# SoM-Supply.net
KiCad netlist of a schematic drawn in Altium Designer
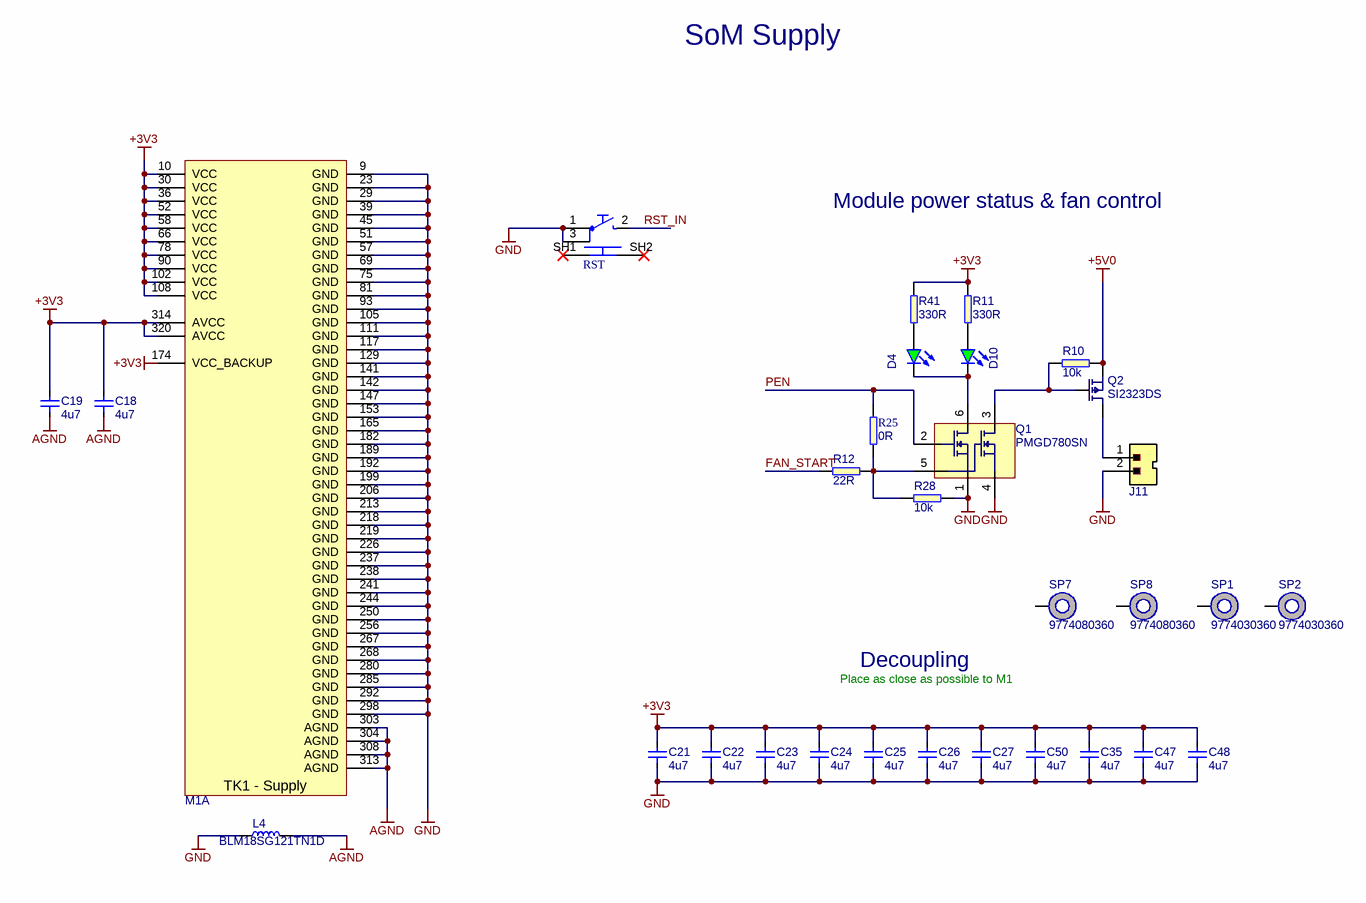
[diagram p0: SoM-Supply.SchDoc]

(export (version "E")
  (design (tool "Eeschema 10.0.6"))
  (components
    (comp (ref "C18")
      (value "4u7")
      (footprint "0603")
      (description "MLCC SMT Capacitor 4.7uF 0603")
      (fields (field (name "MANUFACTURER") "MULTICOMP") (field (name "PART NUMBER") "C_4u7_0603"))
      (libsource (lib "TK1Baseboard") (part "C_4u7_0603"))
    )
    (comp (ref "C19")
      (value "4u7")
      (footprint "0603")
      (description "MLCC SMT Capacitor 4.7uF 0603")
      (fields (field (name "MANUFACTURER") "MULTICOMP") (field (name "PART NUMBER") "C_4u7_0603"))
      (libsource (lib "TK1Baseboard") (part "C_4u7_0603"))
    )
    (comp (ref "C21")
      (value "4u7")
      (footprint "0603")
      (description "MLCC SMT Capacitor 4.7uF 0603")
      (fields (field (name "MANUFACTURER") "MULTICOMP") (field (name "PART NUMBER") "C_4u7_0603"))
      (libsource (lib "TK1Baseboard") (part "C_4u7_0603"))
    )
    (comp (ref "C22")
      (value "4u7")
      (footprint "0603")
      (description "MLCC SMT Capacitor 4.7uF 0603")
      (fields (field (name "MANUFACTURER") "MULTICOMP") (field (name "PART NUMBER") "C_4u7_0603"))
      (libsource (lib "TK1Baseboard") (part "C_4u7_0603"))
    )
    (comp (ref "C23")
      (value "4u7")
      (footprint "0603")
      (description "MLCC SMT Capacitor 4.7uF 0603")
      (fields (field (name "MANUFACTURER") "MULTICOMP") (field (name "PART NUMBER") "C_4u7_0603"))
      (libsource (lib "TK1Baseboard") (part "C_4u7_0603"))
    )
    (comp (ref "C24")
      (value "4u7")
      (footprint "0603")
      (description "MLCC SMT Capacitor 4.7uF 0603")
      (fields (field (name "MANUFACTURER") "MULTICOMP") (field (name "PART NUMBER") "C_4u7_0603"))
      (libsource (lib "TK1Baseboard") (part "C_4u7_0603"))
    )
    (comp (ref "C25")
      (value "4u7")
      (footprint "0603")
      (description "MLCC SMT Capacitor 4.7uF 0603")
      (fields (field (name "MANUFACTURER") "MULTICOMP") (field (name "PART NUMBER") "C_4u7_0603"))
      (libsource (lib "TK1Baseboard") (part "C_4u7_0603"))
    )
    (comp (ref "C26")
      (value "4u7")
      (footprint "0603")
      (description "MLCC SMT Capacitor 4.7uF 0603")
      (fields (field (name "MANUFACTURER") "MULTICOMP") (field (name "PART NUMBER") "C_4u7_0603"))
      (libsource (lib "TK1Baseboard") (part "C_4u7_0603"))
    )
    (comp (ref "C27")
      (value "4u7")
      (footprint "0603")
      (description "MLCC SMT Capacitor 4.7uF 0603")
      (fields (field (name "MANUFACTURER") "MULTICOMP") (field (name "PART NUMBER") "C_4u7_0603"))
      (libsource (lib "TK1Baseboard") (part "C_4u7_0603"))
    )
    (comp (ref "C35")
      (value "4u7")
      (footprint "0603")
      (description "MLCC SMT Capacitor 4.7uF 0603")
      (fields (field (name "MANUFACTURER") "MULTICOMP") (field (name "PART NUMBER") "C_4u7_0603"))
      (libsource (lib "TK1Baseboard") (part "C_4u7_0603"))
    )
    (comp (ref "C47")
      (value "4u7")
      (footprint "0603")
      (description "MLCC SMT Capacitor 4.7uF 0603")
      (fields (field (name "MANUFACTURER") "MULTICOMP") (field (name "PART NUMBER") "C_4u7_0603"))
      (libsource (lib "TK1Baseboard") (part "C_4u7_0603"))
    )
    (comp (ref "C48")
      (value "4u7")
      (footprint "0603")
      (description "MLCC SMT Capacitor 4.7uF 0603")
      (fields (field (name "MANUFACTURER") "MULTICOMP") (field (name "PART NUMBER") "C_4u7_0603"))
      (libsource (lib "TK1Baseboard") (part "C_4u7_0603"))
    )
    (comp (ref "C50")
      (value "4u7")
      (footprint "0603")
      (description "MLCC SMT Capacitor 4.7uF 0603")
      (fields (field (name "MANUFACTURER") "MULTICOMP") (field (name "PART NUMBER") "C_4u7_0603"))
      (libsource (lib "TK1Baseboard") (part "C_4u7_0603"))
    )
    (comp (ref "D4")
      (value "KPT-1608SGC")
      (footprint "LED0603")
      (description "LED Green 0603 case")
      (fields (field (name "PART NUMBER") "LED_G") (field (name "MANUFACTURER") "KINGBRIGHT"))
      (libsource (lib "TK1Baseboard") (part "LED_G"))
    )
    (comp (ref "D10")
      (value "KPT-1608SGC")
      (footprint "LED0603")
      (description "LED Green 0603 case")
      (fields (field (name "PART NUMBER") "LED_G") (field (name "MANUFACTURER") "KINGBRIGHT"))
      (libsource (lib "TK1Baseboard") (part "LED_G"))
    )
    (comp (ref "J11")
      (value "MX-22-23-2021")
      (footprint "molex_2223-2021")
      (description "Pinhead connector with key")
      (fields (field (name "PART NUMBER") "molex_2223-2021") (field (name "MANUFACTURER") "Molex"))
      (libsource (lib "TK1Baseboard") (part "molex_2223-2021"))
    )
    (comp (ref "L4")
      (value "BLM18SG121TN1D")
      (footprint "0603")
      (description "FERRITE BEAD, 0.025OHM, 3A, 0603")
      (fields (field (name "MANUFACTURER") "MURATA"))
      (libsource (lib "TK1Baseboard") (part "BLM18SG121TN1D"))
    )
    (comp (ref "M1")
      (value "MM70-314-310B1")
      (footprint "Apalis-H")
      (description "Toradex Apalis TK1, Horizontal")
      (fields (field (name "PART NUMBER") "Apalis-TK1-H") (field (name "MANUFACTURER") "JAE Electronics"))
      (libsource (lib "TK1Baseboard") (part "Apalis-TK1-H"))
    )
    (comp (ref "Q1")
      (value "PMGD780SN")
      (footprint "SOT-363")
      (description "60 V, dual N-channel Trench MOSFET")
      (fields (field (name "MANUFACTURER") "NXP") (field (name "MPN") "PMGD780SN,115"))
      (libsource (lib "TK1Baseboard") (part "PMGD780SN"))
    )
    (comp (ref "Q2")
      (value "SI2323DS")
      (footprint "SOT-23")
      (description "pMOS 4.7A 20V")
      (fields (field (name "MANUFACTURER") "Vishay") (field (name "MPN") "SI2323DS-T1-E3"))
      (libsource (lib "TK1Baseboard") (part "PMOS"))
    )
    (comp (ref "R10")
      (value "10k")
      (footprint "0402")
      (description "RES, 10k, 0402")
      (fields (field (name "MANUFACTURER") "MULTICOMP") (field (name "PART NUMBER") "R_10k_0402"))
      (libsource (lib "TK1Baseboard") (part "R_10k_0402"))
    )
    (comp (ref "R11")
      (value "330R")
      (footprint "0402")
      (description "RES, 330R, 0402")
      (fields (field (name "MANUFACTURER") "MULTICOMP") (field (name "PART NUMBER") "R_330R_0402"))
      (libsource (lib "TK1Baseboard") (part "R_330R_0402"))
    )
    (comp (ref "R12")
      (value "22R")
      (footprint "0402")
      (description "RES, 22R, 0402")
      (fields (field (name "MANUFACTURER") "VISHAY") (field (name "PART NUMBER") "R_22R_0402"))
      (libsource (lib "TK1Baseboard") (part "R_22R_0402"))
    )
    (comp (ref "R25")
      (value "0R")
      (footprint "0402")
      (description "RES, 0R, 0402")
      (fields (field (name "MANUFACTURER") "Panasonic") (field (name "PART NUMBER") "R_0R_0402"))
      (libsource (lib "TK1Baseboard") (part "R_0R_0402"))
    )
    (comp (ref "R28")
      (value "10k")
      (footprint "0402")
      (description "RES, 10k, 0402")
      (fields (field (name "MANUFACTURER") "MULTICOMP") (field (name "PART NUMBER") "R_10k_0402"))
      (libsource (lib "TK1Baseboard") (part "R_10k_0402"))
    )
    (comp (ref "R41")
      (value "330R")
      (footprint "0402")
      (description "RES, 330R, 0402")
      (fields (field (name "MANUFACTURER") "MULTICOMP") (field (name "PART NUMBER") "R_330R_0402"))
      (libsource (lib "TK1Baseboard") (part "R_330R_0402"))
    )
    (comp (ref "RST")
      (value "TL3340AF160QG")
      (footprint "TL3340AF160QG")
      (description "E-SWITCH  TL3340AF160QG  SWITCH, TACTILE SPST 50mA, SMD GULL WING")
      (fields (field (name "MANUFACTURER") "E-SWITCH"))
      (libsource (lib "TK1Baseboard") (part "TL3340AF160QG"))
    )
    (comp (ref "SP1")
      (value "9774030360")
      (footprint "M3-3mm")
      (description "M3x3")
      (fields (field (name "PART NUMBER") "WE_9774030360") (field (name "MANUFACTURER") "WURTH ELEKTRONIK"))
      (libsource (lib "TK1Baseboard") (part "WE_9774030360"))
    )
    (comp (ref "SP2")
      (value "9774030360")
      (footprint "M3-3mm")
      (description "M3x3")
      (fields (field (name "PART NUMBER") "WE_9774030360") (field (name "MANUFACTURER") "WURTH ELEKTRONIK"))
      (libsource (lib "TK1Baseboard") (part "WE_9774030360"))
    )
    (comp (ref "SP7")
      (value "9774080360")
      (footprint "M3-8mm")
      (description "M2.5x5")
      (fields (field (name "MANUFACTURER") "WURTH ELEKTRONIK"))
      (libsource (lib "TK1Baseboard") (part "M3x8"))
    )
    (comp (ref "SP8")
      (value "9774080360")
      (footprint "M3-8mm")
      (description "M2.5x5")
      (fields (field (name "MANUFACTURER") "WURTH ELEKTRONIK"))
      (libsource (lib "TK1Baseboard") (part "M3x8"))
    )
  )
  (nets
    (net (code "1") (name "+3V3") (class "Default")
      (node (ref "C18") (pin "2") (pinfunction "2_2") (pintype "passive"))
      (node (ref "C19") (pin "2") (pinfunction "2_2") (pintype "passive"))
      (node (ref "C21") (pin "2") (pinfunction "2_2") (pintype "passive"))
      (node (ref "C22") (pin "2") (pinfunction "2_2") (pintype "passive"))
      (node (ref "C23") (pin "2") (pinfunction "2_2") (pintype "passive"))
      (node (ref "C24") (pin "2") (pinfunction "2_2") (pintype "passive"))
      (node (ref "C25") (pin "2") (pinfunction "2_2") (pintype "passive"))
      (node (ref "C26") (pin "2") (pinfunction "2_2") (pintype "passive"))
      (node (ref "C27") (pin "2") (pinfunction "2_2") (pintype "passive"))
      (node (ref "C35") (pin "2") (pinfunction "2_2") (pintype "passive"))
      (node (ref "C47") (pin "2") (pinfunction "2_2") (pintype "passive"))
      (node (ref "C48") (pin "2") (pinfunction "2_2") (pintype "passive"))
      (node (ref "C50") (pin "2") (pinfunction "2_2") (pintype "passive"))
      (node (ref "M1") (pin "10") (pinfunction "VCC_10") (pintype "passive"))
      (node (ref "M1") (pin "102") (pinfunction "VCC_102") (pintype "passive"))
      (node (ref "M1") (pin "108") (pinfunction "VCC_108") (pintype "passive"))
      (node (ref "M1") (pin "174") (pinfunction "VCC_BACKUP_174") (pintype "passive"))
      (node (ref "M1") (pin "30") (pinfunction "VCC_30") (pintype "passive"))
      (node (ref "M1") (pin "314") (pinfunction "AVCC_314") (pintype "power_in"))
      (node (ref "M1") (pin "320") (pinfunction "AVCC_320") (pintype "passive"))
      (node (ref "M1") (pin "36") (pinfunction "VCC_36") (pintype "passive"))
      (node (ref "M1") (pin "52") (pinfunction "VCC_52") (pintype "passive"))
      (node (ref "M1") (pin "58") (pinfunction "VCC_58") (pintype "passive"))
      (node (ref "M1") (pin "66") (pinfunction "VCC_66") (pintype "passive"))
      (node (ref "M1") (pin "78") (pinfunction "VCC_78") (pintype "passive"))
      (node (ref "M1") (pin "90") (pinfunction "VCC_90") (pintype "passive"))
      (node (ref "R11") (pin "2") (pintype "passive"))
      (node (ref "R41") (pin "2") (pintype "passive"))
    )
    (net (code "2") (name "+5V0") (class "Default")
      (node (ref "Q2") (pin "2") (pinfunction "S_2") (pintype "passive"))
      (node (ref "R10") (pin "2") (pintype "passive"))
    )
    (net (code "3") (name "/FAN_START") (class "Default") (node (ref "R12") (pin "1") (pintype "passive")))
    (net (code "4") (name "/PEN") (class "Default")
      (node (ref "Q1") (pin "2") (pinfunction "G1_2") (pintype "passive"))
      (node (ref "R25") (pin "2") (pintype "passive"))
    )
    (net (code "5") (name "/RST_IN") (class "Default")
      (node (ref "RST") (pin "2") (pinfunction "2_2") (pintype "passive"))
    )
    (net (code "6") (name "AGND") (class "Default")
      (node (ref "C18") (pin "1") (pinfunction "1_1") (pintype "passive"))
      (node (ref "C19") (pin "1") (pinfunction "1_1") (pintype "passive"))
      (node (ref "L4") (pin "2") (pintype "passive"))
      (node (ref "M1") (pin "303") (pinfunction "AGND_303") (pintype "power_in"))
      (node (ref "M1") (pin "304") (pinfunction "AGND_304") (pintype "power_in"))
      (node (ref "M1") (pin "308") (pinfunction "AGND_308") (pintype "power_in"))
      (node (ref "M1") (pin "313") (pinfunction "AGND_313") (pintype "passive"))
    )
    (net (code "7") (name "GND") (class "Default")
      (node (ref "C21") (pin "1") (pinfunction "1_1") (pintype "passive"))
      (node (ref "C22") (pin "1") (pinfunction "1_1") (pintype "passive"))
      (node (ref "C23") (pin "1") (pinfunction "1_1") (pintype "passive"))
      (node (ref "C24") (pin "1") (pinfunction "1_1") (pintype "passive"))
      (node (ref "C25") (pin "1") (pinfunction "1_1") (pintype "passive"))
      (node (ref "C26") (pin "1") (pinfunction "1_1") (pintype "passive"))
      (node (ref "C27") (pin "1") (pinfunction "1_1") (pintype "passive"))
      (node (ref "C35") (pin "1") (pinfunction "1_1") (pintype "passive"))
      (node (ref "C47") (pin "1") (pinfunction "1_1") (pintype "passive"))
      (node (ref "C48") (pin "1") (pinfunction "1_1") (pintype "passive"))
      (node (ref "C50") (pin "1") (pinfunction "1_1") (pintype "passive"))
      (node (ref "J11") (pin "2") (pinfunction "2_2") (pintype "passive"))
      (node (ref "L4") (pin "1") (pintype "passive"))
      (node (ref "M1") (pin "105") (pinfunction "GND_105") (pintype "power_in"))
      (node (ref "M1") (pin "111") (pinfunction "GND_111") (pintype "power_in"))
      (node (ref "M1") (pin "117") (pinfunction "GND_117") (pintype "power_in"))
      (node (ref "M1") (pin "129") (pinfunction "GND_129") (pintype "power_in"))
      (node (ref "M1") (pin "141") (pinfunction "GND_141") (pintype "power_in"))
      (node (ref "M1") (pin "142") (pinfunction "GND_142") (pintype "power_in"))
      (node (ref "M1") (pin "147") (pinfunction "GND_147") (pintype "power_in"))
      (node (ref "M1") (pin "153") (pinfunction "GND_153") (pintype "power_in"))
      (node (ref "M1") (pin "165") (pinfunction "GND_165") (pintype "power_in"))
      (node (ref "M1") (pin "182") (pinfunction "GND_182") (pintype "power_in"))
      (node (ref "M1") (pin "189") (pinfunction "GND_189") (pintype "power_in"))
      (node (ref "M1") (pin "192") (pinfunction "GND_192") (pintype "power_in"))
      (node (ref "M1") (pin "199") (pinfunction "GND_199") (pintype "power_in"))
      (node (ref "M1") (pin "206") (pinfunction "GND_206") (pintype "power_in"))
      (node (ref "M1") (pin "213") (pinfunction "GND_213") (pintype "power_in"))
      (node (ref "M1") (pin "218") (pinfunction "GND_218") (pintype "power_in"))
      (node (ref "M1") (pin "219") (pinfunction "GND_219") (pintype "power_in"))
      (node (ref "M1") (pin "226") (pinfunction "GND_226") (pintype "power_in"))
      (node (ref "M1") (pin "23") (pinfunction "GND_23") (pintype "passive"))
      (node (ref "M1") (pin "237") (pinfunction "GND_237") (pintype "power_in"))
      (node (ref "M1") (pin "238") (pinfunction "GND_238") (pintype "power_in"))
      (node (ref "M1") (pin "241") (pinfunction "GND_241") (pintype "power_in"))
      (node (ref "M1") (pin "244") (pinfunction "GND_244") (pintype "power_in"))
      (node (ref "M1") (pin "250") (pinfunction "GND_250") (pintype "power_in"))
      (node (ref "M1") (pin "256") (pinfunction "GND_256") (pintype "power_in"))
      (node (ref "M1") (pin "267") (pinfunction "GND_267") (pintype "power_in"))
      (node (ref "M1") (pin "268") (pinfunction "GND_268") (pintype "power_in"))
      (node (ref "M1") (pin "280") (pinfunction "GND_280") (pintype "power_in"))
      (node (ref "M1") (pin "285") (pinfunction "GND_285") (pintype "power_in"))
      (node (ref "M1") (pin "29") (pinfunction "GND_29") (pintype "power_in"))
      (node (ref "M1") (pin "292") (pinfunction "GND_292") (pintype "power_in"))
      (node (ref "M1") (pin "298") (pinfunction "GND_298") (pintype "power_in"))
      (node (ref "M1") (pin "39") (pinfunction "GND_39") (pintype "power_in"))
      (node (ref "M1") (pin "45") (pinfunction "GND_45") (pintype "power_in"))
      (node (ref "M1") (pin "51") (pinfunction "GND_51") (pintype "power_in"))
      (node (ref "M1") (pin "57") (pinfunction "GND_57") (pintype "power_in"))
      (node (ref "M1") (pin "69") (pinfunction "GND_69") (pintype "power_in"))
      (node (ref "M1") (pin "75") (pinfunction "GND_75") (pintype "power_in"))
      (node (ref "M1") (pin "81") (pinfunction "GND_81") (pintype "power_in"))
      (node (ref "M1") (pin "9") (pinfunction "GND_9") (pintype "passive"))
      (node (ref "M1") (pin "93") (pinfunction "GND_93") (pintype "power_in"))
      (node (ref "Q1") (pin "1") (pinfunction "S1_1") (pintype "passive"))
      (node (ref "Q1") (pin "4") (pinfunction "S2_4") (pintype "passive"))
      (node (ref "R28") (pin "2") (pintype "passive"))
      (node (ref "RST") (pin "1") (pinfunction "1_1") (pintype "passive"))
      (node (ref "RST") (pin "3") (pinfunction "3_3") (pintype "passive"))
    )
    (net (code "8") (name "Net-(D4-PadA)") (class "Default")
      (node (ref "D4") (pin "A") (pinfunction "A_A") (pintype "passive"))
      (node (ref "R41") (pin "1") (pintype "passive"))
    )
    (net (code "9") (name "Net-(D10-PadA)") (class "Default")
      (node (ref "D10") (pin "A") (pinfunction "A_A") (pintype "passive"))
      (node (ref "R11") (pin "1") (pintype "passive"))
    )
    (net (code "10") (name "Net-(Q1-D1)") (class "Default")
      (node (ref "D10") (pin "K") (pinfunction "K_K") (pintype "passive"))
      (node (ref "D4") (pin "K") (pinfunction "K_K") (pintype "passive"))
      (node (ref "Q1") (pin "6") (pinfunction "D1_6") (pintype "passive"))
    )
    (net (code "11") (name "Net-(Q1-D2)") (class "Default")
      (node (ref "Q1") (pin "3") (pinfunction "D2_3") (pintype "passive"))
      (node (ref "Q2") (pin "1") (pinfunction "G_1") (pintype "passive"))
      (node (ref "R10") (pin "1") (pintype "passive"))
    )
    (net (code "12") (name "Net-(Q1-G2)") (class "Default")
      (node (ref "Q1") (pin "5") (pinfunction "G2_5") (pintype "passive"))
      (node (ref "R12") (pin "2") (pintype "passive"))
      (node (ref "R25") (pin "1") (pintype "passive"))
      (node (ref "R28") (pin "1") (pintype "passive"))
    )
    (net (code "13") (name "Net-(Q2-D)") (class "Default")
      (node (ref "J11") (pin "1") (pinfunction "1_1") (pintype "passive"))
      (node (ref "Q2") (pin "3") (pinfunction "D_3") (pintype "passive"))
    )
    (net (code "14") (name "unconnected-(RST-PadSH1)") (class "Default")
      (node (ref "RST") (pin "SH1") (pinfunction "SH1_SH1") (pintype "passive+no_connect"))
    )
    (net (code "15") (name "unconnected-(RST-PadSH2)") (class "Default")
      (node (ref "RST") (pin "SH2") (pinfunction "SH2_SH2") (pintype "passive+no_connect"))
    )
    (net (code "16") (name "unconnected-(SP1-Pad1)") (class "Default")
      (node (ref "SP1") (pin "1") (pinfunction "1_1") (pintype "passive"))
    )
    (net (code "17") (name "unconnected-(SP2-Pad1)") (class "Default")
      (node (ref "SP2") (pin "1") (pinfunction "1_1") (pintype "passive"))
    )
    (net (code "18") (name "unconnected-(SP7-Pad1)") (class "Default")
      (node (ref "SP7") (pin "1") (pinfunction "1_1") (pintype "passive"))
    )
    (net (code "19") (name "unconnected-(SP8-Pad1)") (class "Default")
      (node (ref "SP8") (pin "1") (pinfunction "1_1") (pintype "passive"))
    )
  )
)
